# Motor2.net
KiCad netlist of a schematic drawn in Altium Designer
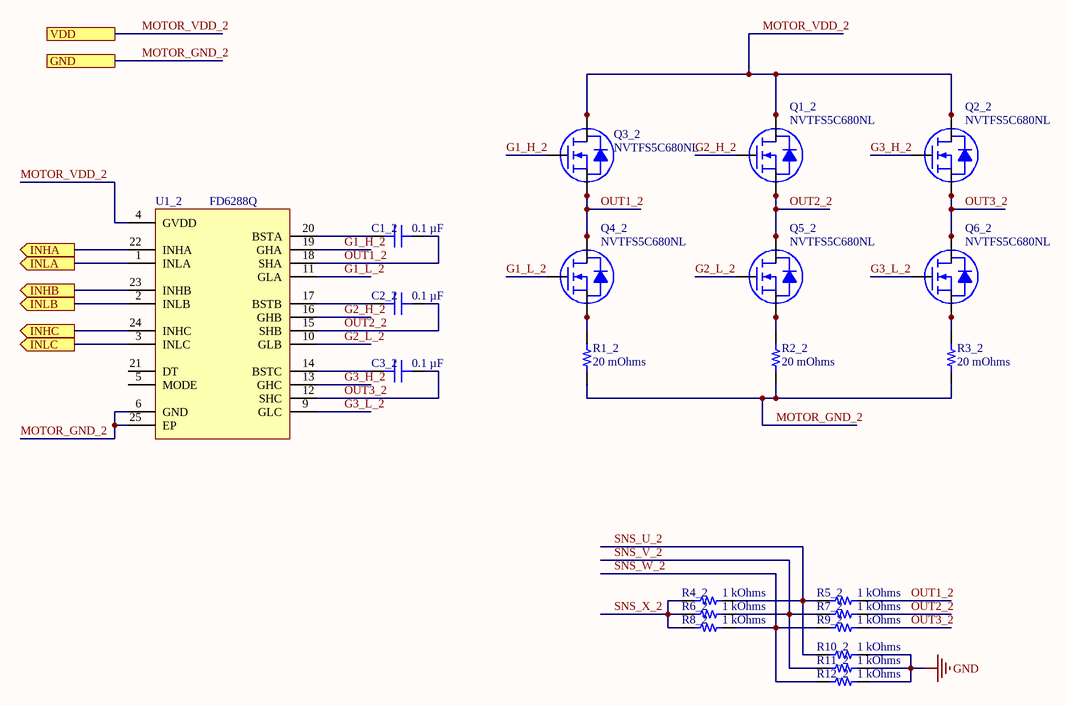
[diagram p0: Motor2.SchDoc]

(export (version "E")
  (design (tool "Eeschema 10.0.6"))
  (components
    (comp (ref "C1_2")
      (value "0.1 µF")
      (footprint "CAP 0402_1005")
      (description "CAP CER 0.1UF 16V X7R 0402")
      (fields (field (name "PART NUMBER") "C0402C104K4RACAUTO") (field (name "MANUFACTURER") "KEMET"))
      (libsource (lib "Celestial Altium Library - altium_library") (part "Capacitor"))
    )
    (comp (ref "C2_2")
      (value "0.1 µF")
      (footprint "CAP 0402_1005")
      (description "CAP CER 0.1UF 16V X7R 0402")
      (fields (field (name "PART NUMBER") "C0402C104K4RACAUTO") (field (name "MANUFACTURER") "KEMET"))
      (libsource (lib "Celestial Altium Library - altium_library") (part "Capacitor"))
    )
    (comp (ref "C3_2")
      (value "0.1 µF")
      (footprint "CAP 0402_1005")
      (description "CAP CER 0.1UF 16V X7R 0402")
      (fields (field (name "PART NUMBER") "C0402C104K4RACAUTO") (field (name "MANUFACTURER") "KEMET"))
      (libsource (lib "Celestial Altium Library - altium_library") (part "Capacitor"))
    )
    (comp (ref "Q1_2")
      (value "NVTFS5C680NL")
      (footprint "NVTFS015N04CTAG")
      (description "N-FET")
      (libsource (lib "IC") (part "NVTFS5C680NL"))
    )
    (comp (ref "Q2_2")
      (value "NVTFS5C680NL")
      (footprint "NVTFS015N04CTAG")
      (description "N-FET")
      (libsource (lib "IC") (part "NVTFS5C680NL"))
    )
    (comp (ref "Q3_2")
      (value "NVTFS5C680NL")
      (footprint "NVTFS015N04CTAG")
      (description "N-FET")
      (libsource (lib "IC") (part "NVTFS5C680NL"))
    )
    (comp (ref "Q4_2")
      (value "NVTFS5C680NL")
      (footprint "NVTFS015N04CTAG")
      (description "N-FET")
      (libsource (lib "IC") (part "NVTFS5C680NL"))
    )
    (comp (ref "Q5_2")
      (value "NVTFS5C680NL")
      (footprint "NVTFS015N04CTAG")
      (description "N-FET")
      (libsource (lib "IC") (part "NVTFS5C680NL"))
    )
    (comp (ref "Q6_2")
      (value "NVTFS5C680NL")
      (footprint "NVTFS015N04CTAG")
      (description "N-FET")
      (libsource (lib "IC") (part "NVTFS5C680NL"))
    )
    (comp (ref "R1_2")
      (value "20 mOhms")
      (footprint "STACKPOLE CSR0805")
      (description "RES 0.02 OHM 1% 1/3W 0603")
      (fields
        (field (name "PART NUMBER") "ERJ-3BWFR020V")
        (field (name "MANUFACTURER") "Panasonic Electronic Components")
      )
      (libsource (lib "Celestial Altium Library - altium_library") (part "Resistor"))
    )
    (comp (ref "R2_2")
      (value "20 mOhms")
      (footprint "STACKPOLE CSR0805")
      (description "RES 0.02 OHM 1% 1/3W 0603")
      (fields
        (field (name "PART NUMBER") "ERJ-3BWFR020V")
        (field (name "MANUFACTURER") "Panasonic Electronic Components")
      )
      (libsource (lib "Celestial Altium Library - altium_library") (part "Resistor"))
    )
    (comp (ref "R3_2")
      (value "20 mOhms")
      (footprint "STACKPOLE CSR0805")
      (description "RES 0.02 OHM 1% 1/3W 0603")
      (fields
        (field (name "PART NUMBER") "ERJ-3BWFR020V")
        (field (name "MANUFACTURER") "Panasonic Electronic Components")
      )
      (libsource (lib "Celestial Altium Library - altium_library") (part "Resistor"))
    )
    (comp (ref "R4_2")
      (value "1 kOhms")
      (footprint "RES 0402_1005")
      (description "RES 14.3K OHM 1% 1/10W 0402")
      (fields
        (field (name "PART NUMBER") "RK73H1ETTP1432F")
        (field (name "MANUFACTURER") "KOA Speer Electronics, Inc.")
      )
      (libsource (lib "Celestial Altium Library - altium_library") (part "Resistor"))
    )
    (comp (ref "R5_2")
      (value "1 kOhms")
      (footprint "RES 0402_1005")
      (description "RES 14.3K OHM 1% 1/10W 0402")
      (fields
        (field (name "PART NUMBER") "RK73H1ETTP1432F")
        (field (name "MANUFACTURER") "KOA Speer Electronics, Inc.")
      )
      (libsource (lib "Celestial Altium Library - altium_library") (part "Resistor"))
    )
    (comp (ref "R6_2")
      (value "1 kOhms")
      (footprint "RES 0402_1005")
      (description "RES 14.3K OHM 1% 1/10W 0402")
      (fields
        (field (name "PART NUMBER") "RK73H1ETTP1432F")
        (field (name "MANUFACTURER") "KOA Speer Electronics, Inc.")
      )
      (libsource (lib "Celestial Altium Library - altium_library") (part "Resistor"))
    )
    (comp (ref "R7_2")
      (value "1 kOhms")
      (footprint "RES 0402_1005")
      (description "RES 14.3K OHM 1% 1/10W 0402")
      (fields
        (field (name "PART NUMBER") "RK73H1ETTP1432F")
        (field (name "MANUFACTURER") "KOA Speer Electronics, Inc.")
      )
      (libsource (lib "Celestial Altium Library - altium_library") (part "Resistor"))
    )
    (comp (ref "R8_2")
      (value "1 kOhms")
      (footprint "RES 0402_1005")
      (description "RES 14.3K OHM 1% 1/10W 0402")
      (fields
        (field (name "PART NUMBER") "RK73H1ETTP1432F")
        (field (name "MANUFACTURER") "KOA Speer Electronics, Inc.")
      )
      (libsource (lib "Celestial Altium Library - altium_library") (part "Resistor"))
    )
    (comp (ref "R9_2")
      (value "1 kOhms")
      (footprint "RES 0402_1005")
      (description "RES 14.3K OHM 1% 1/10W 0402")
      (fields
        (field (name "PART NUMBER") "RK73H1ETTP1432F")
        (field (name "MANUFACTURER") "KOA Speer Electronics, Inc.")
      )
      (libsource (lib "Celestial Altium Library - altium_library") (part "Resistor"))
    )
    (comp (ref "R10_2")
      (value "1 kOhms")
      (footprint "RES 0402_1005")
      (description "RES 14.3K OHM 1% 1/10W 0402")
      (fields
        (field (name "PART NUMBER") "RK73H1ETTP1432F")
        (field (name "MANUFACTURER") "KOA Speer Electronics, Inc.")
      )
      (libsource (lib "Celestial Altium Library - altium_library") (part "Resistor"))
    )
    (comp (ref "R11_2")
      (value "1 kOhms")
      (footprint "RES 0402_1005")
      (description "RES 14.3K OHM 1% 1/10W 0402")
      (fields
        (field (name "PART NUMBER") "RK73H1ETTP1432F")
        (field (name "MANUFACTURER") "KOA Speer Electronics, Inc.")
      )
      (libsource (lib "Celestial Altium Library - altium_library") (part "Resistor"))
    )
    (comp (ref "R12_2")
      (value "1 kOhms")
      (footprint "RES 0402_1005")
      (description "RES 14.3K OHM 1% 1/10W 0402")
      (fields
        (field (name "PART NUMBER") "RK73H1ETTP1432F")
        (field (name "MANUFACTURER") "KOA Speer Electronics, Inc.")
      )
      (libsource (lib "Celestial Altium Library - altium_library") (part "Resistor"))
    )
    (comp (ref "U1_2")
      (value "FD6288Q")
      (footprint "QFN50P400X400X100-25N")
      (description "3 Phase Gate Driver 1.5-2.2A")
      (fields (field (name "MF") "Texas Instruments") (field (name "MP") "UCC27282DRCR"))
      (libsource (lib "IC") (part "FD6288Q"))
    )
  )
  (nets
    (net (code "1") (name "/G1_H_2") (class "Default")
      (node (ref "Q3_2") (pin "4") (pinfunction "G_4") (pintype "passive"))
      (node (ref "U1_2") (pin "19") (pinfunction "GHA_19") (pintype "passive"))
    )
    (net (code "2") (name "/G1_L_2") (class "Default")
      (node (ref "Q4_2") (pin "4") (pinfunction "G_4") (pintype "passive"))
      (node (ref "U1_2") (pin "11") (pinfunction "GLA_11") (pintype "passive"))
    )
    (net (code "3") (name "/G2_H_2") (class "Default")
      (node (ref "Q1_2") (pin "4") (pinfunction "G_4") (pintype "passive"))
      (node (ref "U1_2") (pin "16") (pinfunction "GHB_16") (pintype "passive"))
    )
    (net (code "4") (name "/G2_L_2") (class "Default")
      (node (ref "Q5_2") (pin "4") (pinfunction "G_4") (pintype "passive"))
      (node (ref "U1_2") (pin "10") (pinfunction "GLB_10") (pintype "passive"))
    )
    (net (code "5") (name "/G3_H_2") (class "Default")
      (node (ref "Q2_2") (pin "4") (pinfunction "G_4") (pintype "passive"))
      (node (ref "U1_2") (pin "13") (pinfunction "GHC_13") (pintype "passive"))
    )
    (net (code "6") (name "/G3_L_2") (class "Default")
      (node (ref "Q6_2") (pin "4") (pinfunction "G_4") (pintype "passive"))
      (node (ref "U1_2") (pin "9") (pinfunction "GLC_9") (pintype "passive"))
    )
    (net (code "7") (name "/INHA") (class "Default")
      (node (ref "U1_2") (pin "22") (pinfunction "INHA_22") (pintype "passive"))
    )
    (net (code "8") (name "/INHB") (class "Default")
      (node (ref "U1_2") (pin "23") (pinfunction "INHB_23") (pintype "passive"))
    )
    (net (code "9") (name "/INHC") (class "Default")
      (node (ref "U1_2") (pin "24") (pinfunction "INHC_24") (pintype "passive"))
    )
    (net (code "10") (name "/INLA") (class "Default")
      (node (ref "U1_2") (pin "1") (pinfunction "INLA_1") (pintype "passive"))
    )
    (net (code "11") (name "/INLB") (class "Default")
      (node (ref "U1_2") (pin "2") (pinfunction "INLB_2") (pintype "passive"))
    )
    (net (code "12") (name "/INLC") (class "Default")
      (node (ref "U1_2") (pin "3") (pinfunction "INLC_3") (pintype "passive"))
    )
    (net (code "13") (name "/MOTOR_VDD_2") (class "Default")
      (node (ref "Q1_2") (pin "5") (pinfunction "D_5") (pintype "passive"))
      (node (ref "Q1_2") (pin "6") (pinfunction "D_6") (pintype "passive"))
      (node (ref "Q1_2") (pin "7") (pinfunction "D_7") (pintype "passive"))
      (node (ref "Q1_2") (pin "8") (pinfunction "D_8") (pintype "passive"))
      (node (ref "Q2_2") (pin "5") (pinfunction "D_5") (pintype "passive"))
      (node (ref "Q2_2") (pin "6") (pinfunction "D_6") (pintype "passive"))
      (node (ref "Q2_2") (pin "7") (pinfunction "D_7") (pintype "passive"))
      (node (ref "Q2_2") (pin "8") (pinfunction "D_8") (pintype "passive"))
      (node (ref "Q3_2") (pin "5") (pinfunction "D_5") (pintype "passive"))
      (node (ref "Q3_2") (pin "6") (pinfunction "D_6") (pintype "passive"))
      (node (ref "Q3_2") (pin "7") (pinfunction "D_7") (pintype "passive"))
      (node (ref "Q3_2") (pin "8") (pinfunction "D_8") (pintype "passive"))
      (node (ref "U1_2") (pin "4") (pinfunction "GVDD_4") (pintype "passive"))
    )
    (net (code "14") (name "/OUT1_2") (class "Default")
      (node (ref "C1_2") (pin "2") (pinfunction "2_2") (pintype "passive"))
      (node (ref "Q3_2") (pin "1") (pinfunction "S_1") (pintype "passive"))
      (node (ref "Q3_2") (pin "2") (pinfunction "S_2") (pintype "passive"))
      (node (ref "Q3_2") (pin "3") (pinfunction "S_3") (pintype "passive"))
      (node (ref "Q4_2") (pin "5") (pinfunction "D_5") (pintype "passive"))
      (node (ref "Q4_2") (pin "6") (pinfunction "D_6") (pintype "passive"))
      (node (ref "Q4_2") (pin "7") (pinfunction "D_7") (pintype "passive"))
      (node (ref "Q4_2") (pin "8") (pinfunction "D_8") (pintype "passive"))
      (node (ref "R5_2") (pin "2") (pinfunction "2_2") (pintype "passive"))
      (node (ref "U1_2") (pin "18") (pinfunction "SHA_18") (pintype "passive"))
    )
    (net (code "15") (name "/OUT2_2") (class "Default")
      (node (ref "C2_2") (pin "2") (pinfunction "2_2") (pintype "passive"))
      (node (ref "Q1_2") (pin "1") (pinfunction "S_1") (pintype "passive"))
      (node (ref "Q1_2") (pin "2") (pinfunction "S_2") (pintype "passive"))
      (node (ref "Q1_2") (pin "3") (pinfunction "S_3") (pintype "passive"))
      (node (ref "Q5_2") (pin "5") (pinfunction "D_5") (pintype "passive"))
      (node (ref "Q5_2") (pin "6") (pinfunction "D_6") (pintype "passive"))
      (node (ref "Q5_2") (pin "7") (pinfunction "D_7") (pintype "passive"))
      (node (ref "Q5_2") (pin "8") (pinfunction "D_8") (pintype "passive"))
      (node (ref "R7_2") (pin "2") (pinfunction "2_2") (pintype "passive"))
      (node (ref "U1_2") (pin "15") (pinfunction "SHB_15") (pintype "passive"))
    )
    (net (code "16") (name "/OUT3_2") (class "Default")
      (node (ref "C3_2") (pin "2") (pinfunction "2_2") (pintype "passive"))
      (node (ref "Q2_2") (pin "1") (pinfunction "S_1") (pintype "passive"))
      (node (ref "Q2_2") (pin "2") (pinfunction "S_2") (pintype "passive"))
      (node (ref "Q2_2") (pin "3") (pinfunction "S_3") (pintype "passive"))
      (node (ref "Q6_2") (pin "5") (pinfunction "D_5") (pintype "passive"))
      (node (ref "Q6_2") (pin "6") (pinfunction "D_6") (pintype "passive"))
      (node (ref "Q6_2") (pin "7") (pinfunction "D_7") (pintype "passive"))
      (node (ref "Q6_2") (pin "8") (pinfunction "D_8") (pintype "passive"))
      (node (ref "R9_2") (pin "2") (pinfunction "2_2") (pintype "passive"))
      (node (ref "U1_2") (pin "12") (pinfunction "SHC_12") (pintype "passive"))
    )
    (net (code "17") (name "/SNS_U_2") (class "Default")
      (node (ref "R10_2") (pin "2") (pinfunction "2_2") (pintype "passive"))
      (node (ref "R4_2") (pin "2") (pinfunction "2_2") (pintype "passive"))
      (node (ref "R5_2") (pin "1") (pinfunction "1_1") (pintype "passive"))
    )
    (net (code "18") (name "/SNS_V_2") (class "Default")
      (node (ref "R11_2") (pin "2") (pinfunction "2_2") (pintype "passive"))
      (node (ref "R6_2") (pin "2") (pinfunction "2_2") (pintype "passive"))
      (node (ref "R7_2") (pin "1") (pinfunction "1_1") (pintype "passive"))
    )
    (net (code "19") (name "/SNS_W_2") (class "Default")
      (node (ref "R12_2") (pin "2") (pinfunction "2_2") (pintype "passive"))
      (node (ref "R8_2") (pin "2") (pinfunction "2_2") (pintype "passive"))
      (node (ref "R9_2") (pin "1") (pinfunction "1_1") (pintype "passive"))
    )
    (net (code "20") (name "/SNS_X_2") (class "Default")
      (node (ref "R4_2") (pin "1") (pinfunction "1_1") (pintype "passive"))
      (node (ref "R6_2") (pin "1") (pinfunction "1_1") (pintype "passive"))
      (node (ref "R8_2") (pin "1") (pinfunction "1_1") (pintype "passive"))
    )
    (net (code "21") (name "GND") (class "Default")
      (node (ref "R10_2") (pin "1") (pinfunction "1_1") (pintype "passive"))
      (node (ref "R11_2") (pin "1") (pinfunction "1_1") (pintype "passive"))
      (node (ref "R12_2") (pin "1") (pinfunction "1_1") (pintype "passive"))
      (node (ref "R1_2") (pin "1") (pinfunction "1_1") (pintype "passive"))
      (node (ref "R2_2") (pin "1") (pinfunction "1_1") (pintype "passive"))
      (node (ref "R3_2") (pin "1") (pinfunction "1_1") (pintype "passive"))
      (node (ref "U1_2") (pin "25") (pinfunction "EP_25") (pintype "passive"))
      (node (ref "U1_2") (pin "6") (pinfunction "GND_6") (pintype "passive"))
    )
    (net (code "22") (name "Net-(Q4_2-S-Pad1)") (class "Default")
      (node (ref "Q4_2") (pin "1") (pinfunction "S_1") (pintype "passive"))
      (node (ref "Q4_2") (pin "2") (pinfunction "S_2") (pintype "passive"))
      (node (ref "Q4_2") (pin "3") (pinfunction "S_3") (pintype "passive"))
      (node (ref "R1_2") (pin "2") (pinfunction "2_2") (pintype "passive"))
    )
    (net (code "23") (name "Net-(Q5_2-S-Pad1)") (class "Default")
      (node (ref "Q5_2") (pin "1") (pinfunction "S_1") (pintype "passive"))
      (node (ref "Q5_2") (pin "2") (pinfunction "S_2") (pintype "passive"))
      (node (ref "Q5_2") (pin "3") (pinfunction "S_3") (pintype "passive"))
      (node (ref "R2_2") (pin "2") (pinfunction "2_2") (pintype "passive"))
    )
    (net (code "24") (name "Net-(Q6_2-S-Pad1)") (class "Default")
      (node (ref "Q6_2") (pin "1") (pinfunction "S_1") (pintype "passive"))
      (node (ref "Q6_2") (pin "2") (pinfunction "S_2") (pintype "passive"))
      (node (ref "Q6_2") (pin "3") (pinfunction "S_3") (pintype "passive"))
      (node (ref "R3_2") (pin "2") (pinfunction "2_2") (pintype "passive"))
    )
    (net (code "25") (name "Net-(U1_2-BSTA)") (class "Default")
      (node (ref "C1_2") (pin "1") (pinfunction "1_1") (pintype "passive"))
      (node (ref "U1_2") (pin "20") (pinfunction "BSTA_20") (pintype "passive"))
    )
    (net (code "26") (name "Net-(U1_2-BSTB)") (class "Default")
      (node (ref "C2_2") (pin "1") (pinfunction "1_1") (pintype "passive"))
      (node (ref "U1_2") (pin "17") (pinfunction "BSTB_17") (pintype "passive"))
    )
    (net (code "27") (name "Net-(U1_2-BSTC)") (class "Default")
      (node (ref "C3_2") (pin "1") (pinfunction "1_1") (pintype "passive"))
      (node (ref "U1_2") (pin "14") (pinfunction "BSTC_14") (pintype "passive"))
    )
    (net (code "28") (name "unconnected-(U1_2-DT-Pad21)") (class "Default")
      (node (ref "U1_2") (pin "21") (pinfunction "DT_21") (pintype "passive"))
    )
    (net (code "29") (name "unconnected-(U1_2-MODE-Pad5)") (class "Default")
      (node (ref "U1_2") (pin "5") (pinfunction "MODE_5") (pintype "passive"))
    )
  )
)
